# Meranie.net
KiCad netlist of a schematic drawn in Altium Designer
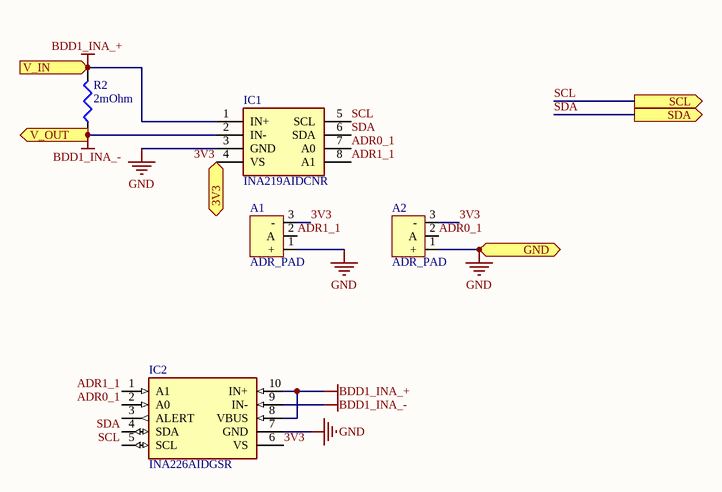
[diagram p0: Meranie.SchDoc]

(export (version "E")
  (design (tool "Eeschema 10.0.6"))
  (components
    (comp (ref "A1")
      (value "ADR_PAD")
      (footprint "SOLDER_PAD")
      (description "ADR PAD 3 PIN")
      (libsource (lib "SCH_Aquatec") (part "ADR_PAD"))
    )
    (comp (ref "A2")
      (value "ADR_PAD")
      (footprint "SOLDER_PAD")
      (description "ADR PAD 3 PIN")
      (libsource (lib "SCH_Aquatec") (part "ADR_PAD"))
    )
    (comp (ref "IC1")
      (value "INA219AIDCNR")
      (footprint "SOT65P280X145-8N")
      (description "Integrated Circuit")
      (fields
        (field (name "MANUFACTURER_PART_NUMBER") "INA219BIDCNR")
        (field (name "MOUSER PART NUMBER") "595-INA219BIDCNR")
      )
      (libsource (lib "*") (part "INA219BIDCNR"))
    )
    (comp (ref "IC2")
      (value "INA226AIDGSR")
      (footprint "SamacSys:SOP50P490X110-10N")
      (description "Integrated Circuit")
      (fields (field (name "MOUSER PART NUMBER") "595-INA226AIDGSR"))
      (libsource (lib "*") (part "INA226AIDGSR"))
    )
    (comp (ref "R2")
      (value "2mOhm")
      (footprint "RESC3216X75N")
      (description "Resistor")
      (fields (field (name "PUBLISHER") "Altium Limited"))
      (libsource (lib "Miscellaneous Devices") (part "Res3"))
    )
  )
  (nets
    (net (code "1") (name "/3V3") (class "Default")
      (node (ref "A1") (pin "3") (pinfunction "-_3") (pintype "passive"))
      (node (ref "A2") (pin "3") (pinfunction "-_3") (pintype "passive"))
      (node (ref "IC1") (pin "4") (pinfunction "VS_4") (pintype "power_in"))
      (node (ref "IC2") (pin "6") (pinfunction "VS_6") (pintype "power_in"))
    )
    (net (code "2") (name "/ADR0_1") (class "Default")
      (node (ref "A2") (pin "2") (pinfunction "A_2") (pintype "passive"))
      (node (ref "IC1") (pin "7") (pinfunction "A0_7") (pintype "passive"))
      (node (ref "IC2") (pin "2") (pinfunction "A0_2") (pintype "input"))
    )
    (net (code "3") (name "/ADR1_1") (class "Default")
      (node (ref "A1") (pin "2") (pinfunction "A_2") (pintype "passive"))
      (node (ref "IC1") (pin "8") (pinfunction "A1_8") (pintype "passive"))
      (node (ref "IC2") (pin "1") (pinfunction "A1_1") (pintype "input"))
    )
    (net (code "4") (name "/SCL") (class "Default")
      (node (ref "IC1") (pin "5") (pinfunction "SCL_5") (pintype "passive"))
      (node (ref "IC2") (pin "5") (pinfunction "SCL_5") (pintype "bidirectional"))
    )
    (net (code "5") (name "/SDA") (class "Default")
      (node (ref "IC1") (pin "6") (pinfunction "SDA_6") (pintype "passive"))
      (node (ref "IC2") (pin "4") (pinfunction "SDA_4") (pintype "bidirectional"))
    )
    (net (code "6") (name "BDD1_INA_+") (class "Default")
      (node (ref "IC1") (pin "1") (pinfunction "IN+_1") (pintype "passive"))
      (node (ref "IC2") (pin "10") (pinfunction "IN+_10") (pintype "input"))
      (node (ref "IC2") (pin "8") (pinfunction "VBUS_8") (pintype "input"))
      (node (ref "R2") (pin "2") (pinfunction "2_2") (pintype "passive"))
    )
    (net (code "7") (name "BDD1_INA_-") (class "Default")
      (node (ref "IC1") (pin "2") (pinfunction "IN-_2") (pintype "passive"))
      (node (ref "IC2") (pin "9") (pinfunction "IN-_9") (pintype "input"))
      (node (ref "R2") (pin "1") (pinfunction "1_1") (pintype "passive"))
    )
    (net (code "8") (name "GND") (class "Default")
      (node (ref "A1") (pin "1") (pinfunction "+_1") (pintype "passive"))
      (node (ref "A2") (pin "1") (pinfunction "+_1") (pintype "passive"))
      (node (ref "IC1") (pin "3") (pinfunction "GND_3") (pintype "power_in"))
      (node (ref "IC2") (pin "7") (pinfunction "GND_7") (pintype "power_in"))
    )
    (net (code "9") (name "unconnected-(IC2-ALERT-Pad3)") (class "Default")
      (node (ref "IC2") (pin "3") (pinfunction "ALERT_3") (pintype "output"))
    )
  )
)
